# 1-Schematic_Gripper_diplomski.net
KiCad netlist of a schematic drawn in EasyEDA
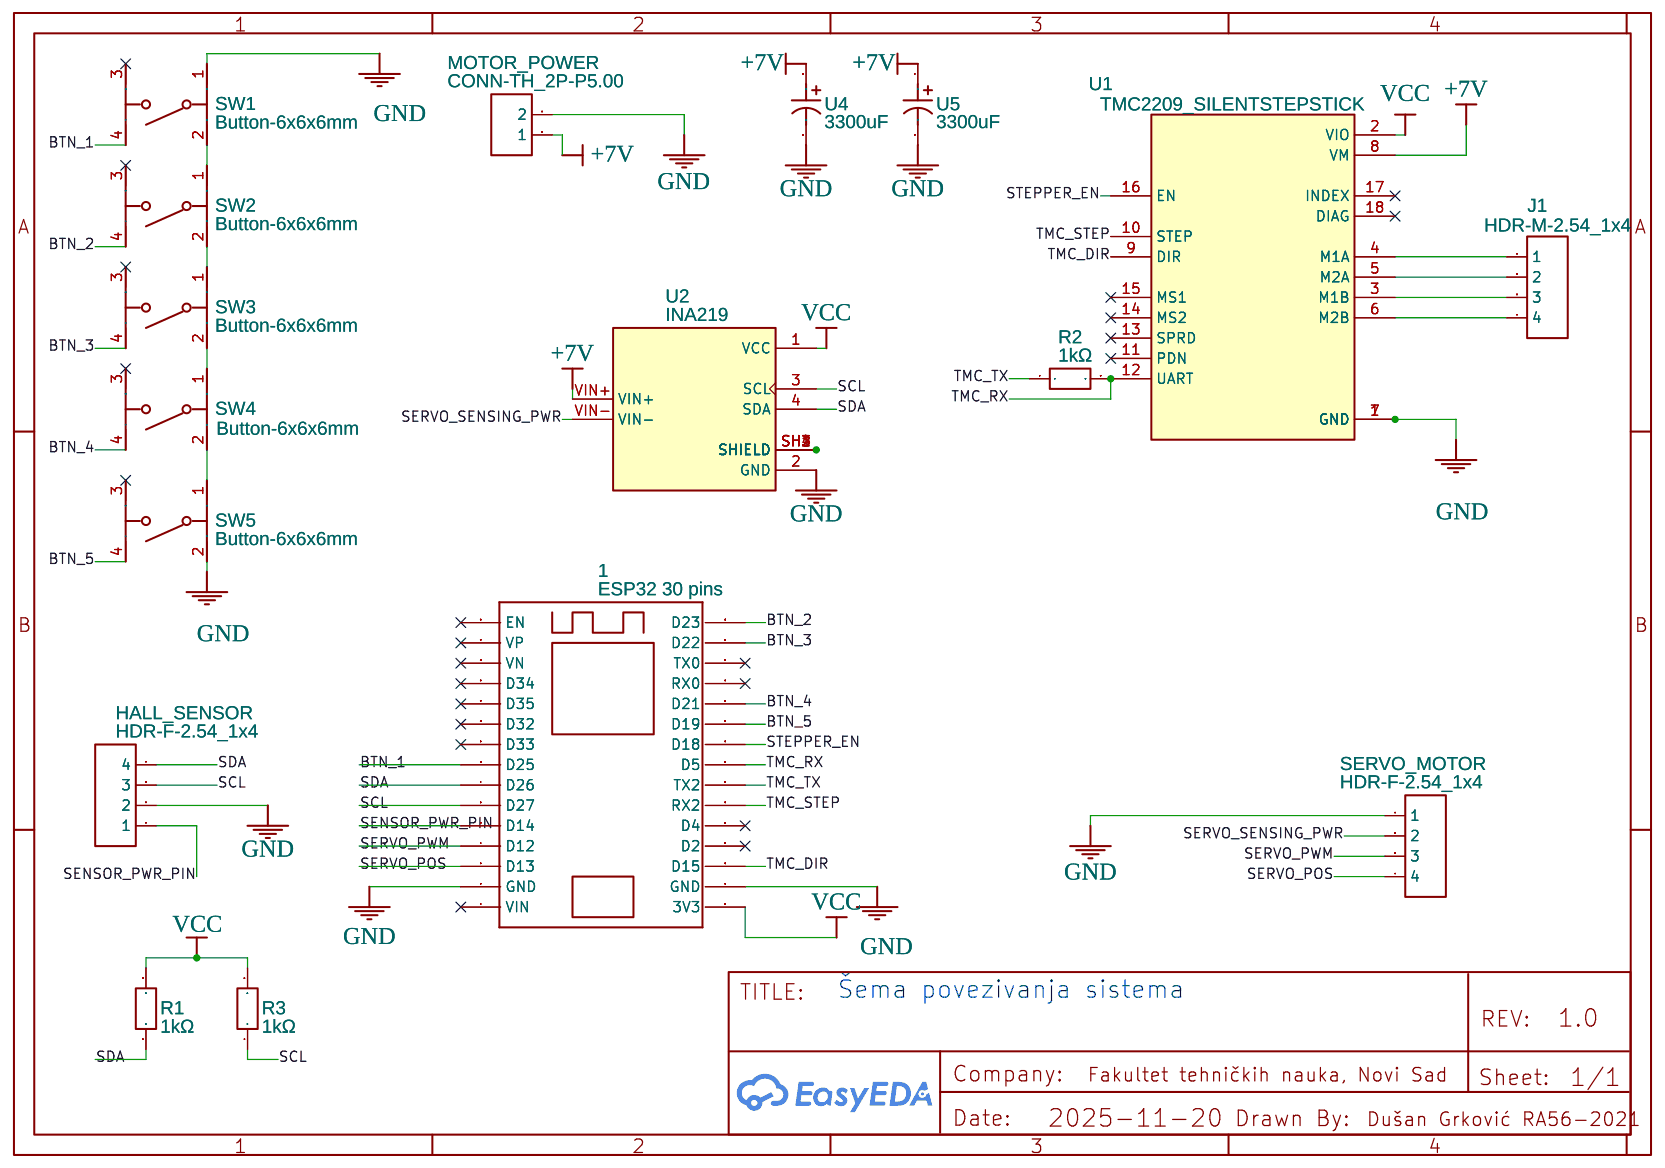
[diagram p0: schematic sheet]

(export (version "E")
  (design (tool "Eeschema 10.0.6"))
  (components
    (comp (ref "1") (value "ESP32 30 pins") (libsource (lib "") (part "ESP32 30 pins")))
    (comp (ref "HALL_SENSOR") (value "HDR-F-2.54_1x4") (libsource (lib "") (part "HDR-F-2.54_1x4")))
    (comp (ref "J1") (value "HDR-M-2.54_1x4") (libsource (lib "") (part "HDR-M-2.54_1x4")))
    (comp (ref "MOTOR_POWER") (value "CONN-TH_2P-P5.00") (libsource (lib "") (part "CONN-TH_2P-P5.00")))
    (comp (ref "R1")
      (value "1kΩ")
      (fields (field (name "Manufacturer Part") "MF0207FTE52-1K") (field (name "Manufacturer") "YAGEO(国巨)"))
      (libsource (lib "") (part "MF0207FTE52-1K_1"))
    )
    (comp (ref "R2")
      (value "1kΩ")
      (fields (field (name "Manufacturer Part") "MF0207FTE52-1K") (field (name "Manufacturer") "YAGEO(国巨)"))
      (libsource (lib "") (part "MF0207FTE52-1K"))
    )
    (comp (ref "R3")
      (value "1kΩ")
      (fields (field (name "Manufacturer Part") "MF0207FTE52-1K") (field (name "Manufacturer") "YAGEO(国巨)"))
      (libsource (lib "") (part "MF0207FTE52-1K_1"))
    )
    (comp (ref "SERVO_MOTOR") (value "HDR-F-2.54_1x4") (libsource (lib "") (part "HDR-F-2.54_1x4_1")))
    (comp (ref "SW1")
      (value "Button-6x6x6mm")
      (fields
        (field (name "Manufacturer Part") "Switch,6*6*6Plastic head,260G, 0.25mm,Straight line")
        (field (name "Manufacturer") "BBJ")
      )
      (libsource (lib "") (part "Button-6x6x6mm"))
    )
    (comp (ref "SW2")
      (value "Button-6x6x6mm")
      (fields
        (field (name "Manufacturer Part") "Switch,6*6*6Plastic head,260G, 0.25mm,Straight line")
        (field (name "Manufacturer") "BBJ")
      )
      (libsource (lib "") (part "Button-6x6x6mm"))
    )
    (comp (ref "SW3")
      (value "Button-6x6x6mm")
      (fields
        (field (name "Manufacturer Part") "Switch,6*6*6Plastic head,260G, 0.25mm,Straight line")
        (field (name "Manufacturer") "BBJ")
      )
      (libsource (lib "") (part "Button-6x6x6mm"))
    )
    (comp (ref "SW4")
      (value "Button-6x6x6mm")
      (fields
        (field (name "Manufacturer Part") "Switch,6*6*6Plastic head,260G, 0.25mm,Straight line")
        (field (name "Manufacturer") "BBJ")
      )
      (libsource (lib "") (part "Button-6x6x6mm"))
    )
    (comp (ref "SW5")
      (value "Button-6x6x6mm")
      (fields
        (field (name "Manufacturer Part") "Switch,6*6*6Plastic head,260G, 0.25mm,Straight line")
        (field (name "Manufacturer") "BBJ")
      )
      (libsource (lib "") (part "Button-6x6x6mm"))
    )
    (comp (ref "U1")
      (value "TMC2209_SILENTSTEPSTICK")
      (fields (field (name "Manufacturer") "Trinamic Motion Control GmbH"))
      (libsource (lib "") (part "TMC2209_SILENTSTEPSTICK"))
    )
    (comp (ref "U2")
      (value "INA219")
      (fields (field (name "Manufacturer") "Adafruit Industries LLC"))
      (libsource (lib "") (part "INA219"))
    )
    (comp (ref "U4")
      (value "3300uF")
      (fields
        (field (name "Manufacturer Part") "16PX3300MEFC12.5X20")
        (field (name "Manufacturer") "rubycon(红宝石)")
      )
      (libsource (lib "") (part "16PX3300MEFC12.5X20"))
    )
    (comp (ref "U5")
      (value "3300uF")
      (fields
        (field (name "Manufacturer Part") "16PX3300MEFC12.5X20")
        (field (name "Manufacturer") "rubycon(红宝石)")
      )
      (libsource (lib "") (part "16PX3300MEFC12.5X20"))
    )
  )
  (nets
    (net (code "1") (name "+7V") (class "Default")
      (node (ref "MOTOR_POWER") (pin "1") (pinfunction "1_1") (pintype "unspecified"))
      (node (ref "U1") (pin "8") (pinfunction "VM_8") (pintype "bidirectional"))
      (node (ref "U2") (pin "VIN+") (pinfunction "VIN+_VIN+") (pintype "input"))
      (node (ref "U4") (pin "1") (pinfunction "1_1") (pintype "input"))
      (node (ref "U5") (pin "1") (pinfunction "1_1") (pintype "input"))
    )
    (net (code "2") (name "/BTN_1") (class "Default")
      (node (ref "1") (pin "8") (pinfunction "D25_8") (pintype "bidirectional"))
      (node (ref "SW1") (pin "4") (pinfunction "4_4") (pintype "unspecified"))
    )
    (net (code "3") (name "/BTN_2") (class "Default")
      (node (ref "1") (pin "30") (pinfunction "D23_30") (pintype "bidirectional"))
      (node (ref "SW2") (pin "4") (pinfunction "4_4") (pintype "unspecified"))
    )
    (net (code "4") (name "/BTN_3") (class "Default")
      (node (ref "1") (pin "29") (pinfunction "D22_29") (pintype "bidirectional"))
      (node (ref "SW3") (pin "4") (pinfunction "4_4") (pintype "unspecified"))
    )
    (net (code "5") (name "/BTN_4") (class "Default")
      (node (ref "1") (pin "26") (pinfunction "D21_26") (pintype "bidirectional"))
      (node (ref "SW4") (pin "4") (pinfunction "4_4") (pintype "unspecified"))
    )
    (net (code "6") (name "/BTN_5") (class "Default")
      (node (ref "1") (pin "25") (pinfunction "D19_25") (pintype "bidirectional"))
      (node (ref "SW5") (pin "4") (pinfunction "4_4") (pintype "unspecified"))
    )
    (net (code "7") (name "/SCL") (class "Default")
      (node (ref "1") (pin "6") (pinfunction "D27_6") (pintype "bidirectional"))
      (node (ref "HALL_SENSOR") (pin "3") (pinfunction "3_3") (pintype "unspecified"))
      (node (ref "R3") (pin "1") (pinfunction "1_1") (pintype "unspecified"))
      (node (ref "U2") (pin "3") (pinfunction "SCL_3") (pintype "input"))
    )
    (net (code "8") (name "/SDA") (class "Default")
      (node (ref "1") (pin "7") (pinfunction "D26_7") (pintype "bidirectional"))
      (node (ref "HALL_SENSOR") (pin "4") (pinfunction "4_4") (pintype "unspecified"))
      (node (ref "R1") (pin "1") (pinfunction "1_1") (pintype "unspecified"))
      (node (ref "U2") (pin "4") (pinfunction "SDA_4") (pintype "bidirectional"))
    )
    (net (code "9") (name "/SENSOR_PWR_PIN") (class "Default")
      (node (ref "1") (pin "5") (pinfunction "D14_5") (pintype "bidirectional"))
      (node (ref "HALL_SENSOR") (pin "1") (pinfunction "1_1") (pintype "unspecified"))
    )
    (net (code "10") (name "/SERVO_POS") (class "Default")
      (node (ref "1") (pin "3") (pinfunction "D13_3") (pintype "bidirectional"))
      (node (ref "SERVO_MOTOR") (pin "4") (pinfunction "4_4") (pintype "unspecified"))
    )
    (net (code "11") (name "/SERVO_PWM") (class "Default")
      (node (ref "1") (pin "4") (pinfunction "D12_4") (pintype "bidirectional"))
      (node (ref "SERVO_MOTOR") (pin "3") (pinfunction "3_3") (pintype "unspecified"))
    )
    (net (code "12") (name "/SERVO_SENSING_PWR") (class "Default")
      (node (ref "SERVO_MOTOR") (pin "2") (pinfunction "2_2") (pintype "unspecified"))
      (node (ref "U2") (pin "VIN-") (pinfunction "VIN-_VIN-") (pintype "input"))
    )
    (net (code "13") (name "/STEPPER_EN") (class "Default")
      (node (ref "1") (pin "24") (pinfunction "D18_24") (pintype "bidirectional"))
      (node (ref "U1") (pin "16") (pinfunction "EN_16") (pintype "input"))
    )
    (net (code "14") (name "/TMC_DIR") (class "Default")
      (node (ref "1") (pin "18") (pinfunction "D15_18") (pintype "bidirectional"))
      (node (ref "U1") (pin "9") (pinfunction "DIR_9") (pintype "input"))
    )
    (net (code "15") (name "/TMC_RX") (class "Default")
      (node (ref "1") (pin "23") (pinfunction "D5_23") (pintype "bidirectional"))
      (node (ref "R2") (pin "2") (pinfunction "2_2") (pintype "unspecified"))
      (node (ref "U1") (pin "12") (pinfunction "UART_12") (pintype "bidirectional"))
    )
    (net (code "16") (name "/TMC_STEP") (class "Default")
      (node (ref "1") (pin "21") (pinfunction "RX2_21") (pintype "bidirectional"))
      (node (ref "U1") (pin "10") (pinfunction "STEP_10") (pintype "input"))
    )
    (net (code "17") (name "/TMC_TX") (class "Default")
      (node (ref "1") (pin "22") (pinfunction "TX2_22") (pintype "bidirectional"))
      (node (ref "R2") (pin "1") (pinfunction "1_1") (pintype "unspecified"))
    )
    (net (code "18") (name "GND") (class "Default")
      (node (ref "1") (pin "17") (pinfunction "GND_17") (pintype "bidirectional"))
      (node (ref "1") (pin "2") (pinfunction "GND_2") (pintype "bidirectional"))
      (node (ref "HALL_SENSOR") (pin "2") (pinfunction "2_2") (pintype "unspecified"))
      (node (ref "MOTOR_POWER") (pin "2") (pinfunction "2_2") (pintype "unspecified"))
      (node (ref "SERVO_MOTOR") (pin "1") (pinfunction "1_1") (pintype "unspecified"))
      (node (ref "SW1") (pin "1") (pinfunction "1_1") (pintype "unspecified"))
      (node (ref "SW5") (pin "2") (pinfunction "2_2") (pintype "unspecified"))
      (node (ref "U1") (pin "1") (pinfunction "GND_1") (pintype "bidirectional"))
      (node (ref "U1") (pin "7") (pinfunction "GND_7") (pintype "bidirectional"))
      (node (ref "U2") (pin "2") (pinfunction "GND_2") (pintype "bidirectional"))
      (node (ref "U4") (pin "2") (pinfunction "2_2") (pintype "input"))
      (node (ref "U5") (pin "2") (pinfunction "2_2") (pintype "input"))
    )
    (net (code "19") (name "Net-(SW1-Pad2)") (class "Default")
      (node (ref "SW1") (pin "2") (pinfunction "2_2") (pintype "unspecified"))
      (node (ref "SW2") (pin "1") (pinfunction "1_1") (pintype "unspecified"))
    )
    (net (code "20") (name "Net-(SW2-Pad2)") (class "Default")
      (node (ref "SW2") (pin "2") (pinfunction "2_2") (pintype "unspecified"))
      (node (ref "SW3") (pin "1") (pinfunction "1_1") (pintype "unspecified"))
    )
    (net (code "21") (name "Net-(SW3-Pad2)") (class "Default")
      (node (ref "SW3") (pin "2") (pinfunction "2_2") (pintype "unspecified"))
      (node (ref "SW4") (pin "1") (pinfunction "1_1") (pintype "unspecified"))
    )
    (net (code "22") (name "Net-(SW4-Pad2)") (class "Default")
      (node (ref "SW4") (pin "2") (pinfunction "2_2") (pintype "unspecified"))
      (node (ref "SW5") (pin "1") (pinfunction "1_1") (pintype "unspecified"))
    )
    (net (code "23") (name "Net-(U1-M1A)") (class "Default")
      (node (ref "J1") (pin "1") (pinfunction "1_1") (pintype "unspecified"))
      (node (ref "U1") (pin "4") (pinfunction "M1A_4") (pintype "output"))
    )
    (net (code "24") (name "Net-(U1-M1B)") (class "Default")
      (node (ref "J1") (pin "3") (pinfunction "3_3") (pintype "unspecified"))
      (node (ref "U1") (pin "3") (pinfunction "M1B_3") (pintype "output"))
    )
    (net (code "25") (name "Net-(U1-M2A)") (class "Default")
      (node (ref "J1") (pin "2") (pinfunction "2_2") (pintype "unspecified"))
      (node (ref "U1") (pin "5") (pinfunction "M2A_5") (pintype "output"))
    )
    (net (code "26") (name "Net-(U1-M2B)") (class "Default")
      (node (ref "J1") (pin "4") (pinfunction "4_4") (pintype "unspecified"))
      (node (ref "U1") (pin "6") (pinfunction "M2B_6") (pintype "output"))
    )
    (net (code "27") (name "Net-(U2-SHIELD-PadSH1)") (class "Default")
      (node (ref "U2") (pin "SH1") (pinfunction "SHIELD_SH1") (pintype "unspecified"))
      (node (ref "U2") (pin "SH2") (pinfunction "SHIELD_SH2") (pintype "unspecified"))
      (node (ref "U2") (pin "SH3") (pinfunction "SHIELD_SH3") (pintype "unspecified"))
      (node (ref "U2") (pin "SH4") (pinfunction "SHIELD_SH4") (pintype "unspecified"))
    )
    (net (code "28") (name "VCC") (class "Default")
      (node (ref "1") (pin "16") (pinfunction "3V3_16") (pintype "bidirectional"))
      (node (ref "R1") (pin "2") (pinfunction "2_2") (pintype "unspecified"))
      (node (ref "R3") (pin "2") (pinfunction "2_2") (pintype "unspecified"))
      (node (ref "U1") (pin "2") (pinfunction "VIO_2") (pintype "bidirectional"))
      (node (ref "U2") (pin "1") (pinfunction "VCC_1") (pintype "bidirectional"))
    )
    (net (code "29") (name "unconnected-(1-D2-Pad19)") (class "Default")
      (node (ref "1") (pin "19") (pinfunction "D2_19") (pintype "bidirectional+no_connect"))
    )
    (net (code "30") (name "unconnected-(1-D4-Pad20)") (class "Default")
      (node (ref "1") (pin "20") (pinfunction "D4_20") (pintype "bidirectional+no_connect"))
    )
    (net (code "31") (name "unconnected-(1-D32-Pad10)") (class "Default")
      (node (ref "1") (pin "10") (pinfunction "D32_10") (pintype "bidirectional+no_connect"))
    )
    (net (code "32") (name "unconnected-(1-D33-Pad9)") (class "Default")
      (node (ref "1") (pin "9") (pinfunction "D33_9") (pintype "bidirectional+no_connect"))
    )
    (net (code "33") (name "unconnected-(1-D34-Pad12)") (class "Default")
      (node (ref "1") (pin "12") (pinfunction "D34_12") (pintype "bidirectional+no_connect"))
    )
    (net (code "34") (name "unconnected-(1-D35-Pad11)") (class "Default")
      (node (ref "1") (pin "11") (pinfunction "D35_11") (pintype "bidirectional+no_connect"))
    )
    (net (code "35") (name "unconnected-(1-EN-Pad15)") (class "Default")
      (node (ref "1") (pin "15") (pinfunction "EN_15") (pintype "bidirectional+no_connect"))
    )
    (net (code "36") (name "unconnected-(1-RX0-Pad27)") (class "Default")
      (node (ref "1") (pin "27") (pinfunction "RX0_27") (pintype "bidirectional+no_connect"))
    )
    (net (code "37") (name "unconnected-(1-TX0-Pad28)") (class "Default")
      (node (ref "1") (pin "28") (pinfunction "TX0_28") (pintype "bidirectional+no_connect"))
    )
    (net (code "38") (name "unconnected-(1-VIN-Pad1)") (class "Default")
      (node (ref "1") (pin "1") (pinfunction "VIN_1") (pintype "bidirectional+no_connect"))
    )
    (net (code "39") (name "unconnected-(1-VN-Pad13)") (class "Default")
      (node (ref "1") (pin "13") (pinfunction "VN_13") (pintype "bidirectional+no_connect"))
    )
    (net (code "40") (name "unconnected-(1-VP-Pad14)") (class "Default")
      (node (ref "1") (pin "14") (pinfunction "VP_14") (pintype "bidirectional+no_connect"))
    )
    (net (code "41") (name "unconnected-(SW1-Pad3)") (class "Default")
      (node (ref "SW1") (pin "3") (pinfunction "3_3") (pintype "unspecified+no_connect"))
    )
    (net (code "42") (name "unconnected-(SW2-Pad3)") (class "Default")
      (node (ref "SW2") (pin "3") (pinfunction "3_3") (pintype "unspecified+no_connect"))
    )
    (net (code "43") (name "unconnected-(SW3-Pad3)") (class "Default")
      (node (ref "SW3") (pin "3") (pinfunction "3_3") (pintype "unspecified+no_connect"))
    )
    (net (code "44") (name "unconnected-(SW4-Pad3)") (class "Default")
      (node (ref "SW4") (pin "3") (pinfunction "3_3") (pintype "unspecified+no_connect"))
    )
    (net (code "45") (name "unconnected-(SW5-Pad3)") (class "Default")
      (node (ref "SW5") (pin "3") (pinfunction "3_3") (pintype "unspecified+no_connect"))
    )
    (net (code "46") (name "unconnected-(U1-DIAG-Pad18)") (class "Default")
      (node (ref "U1") (pin "18") (pinfunction "DIAG_18") (pintype "output+no_connect"))
    )
    (net (code "47") (name "unconnected-(U1-INDEX-Pad17)") (class "Default")
      (node (ref "U1") (pin "17") (pinfunction "INDEX_17") (pintype "output+no_connect"))
    )
    (net (code "48") (name "unconnected-(U1-MS1-Pad15)") (class "Default")
      (node (ref "U1") (pin "15") (pinfunction "MS1_15") (pintype "input+no_connect"))
    )
    (net (code "49") (name "unconnected-(U1-MS2-Pad14)") (class "Default")
      (node (ref "U1") (pin "14") (pinfunction "MS2_14") (pintype "input+no_connect"))
    )
    (net (code "50") (name "unconnected-(U1-PDN-Pad11)") (class "Default")
      (node (ref "U1") (pin "11") (pinfunction "PDN_11") (pintype "bidirectional+no_connect"))
    )
    (net (code "51") (name "unconnected-(U1-SPRD-Pad13)") (class "Default")
      (node (ref "U1") (pin "13") (pinfunction "SPRD_13") (pintype "input+no_connect"))
    )
  )
)
